# gpi-viper.net
KiCad netlist of a schematic drawn in EAGLE
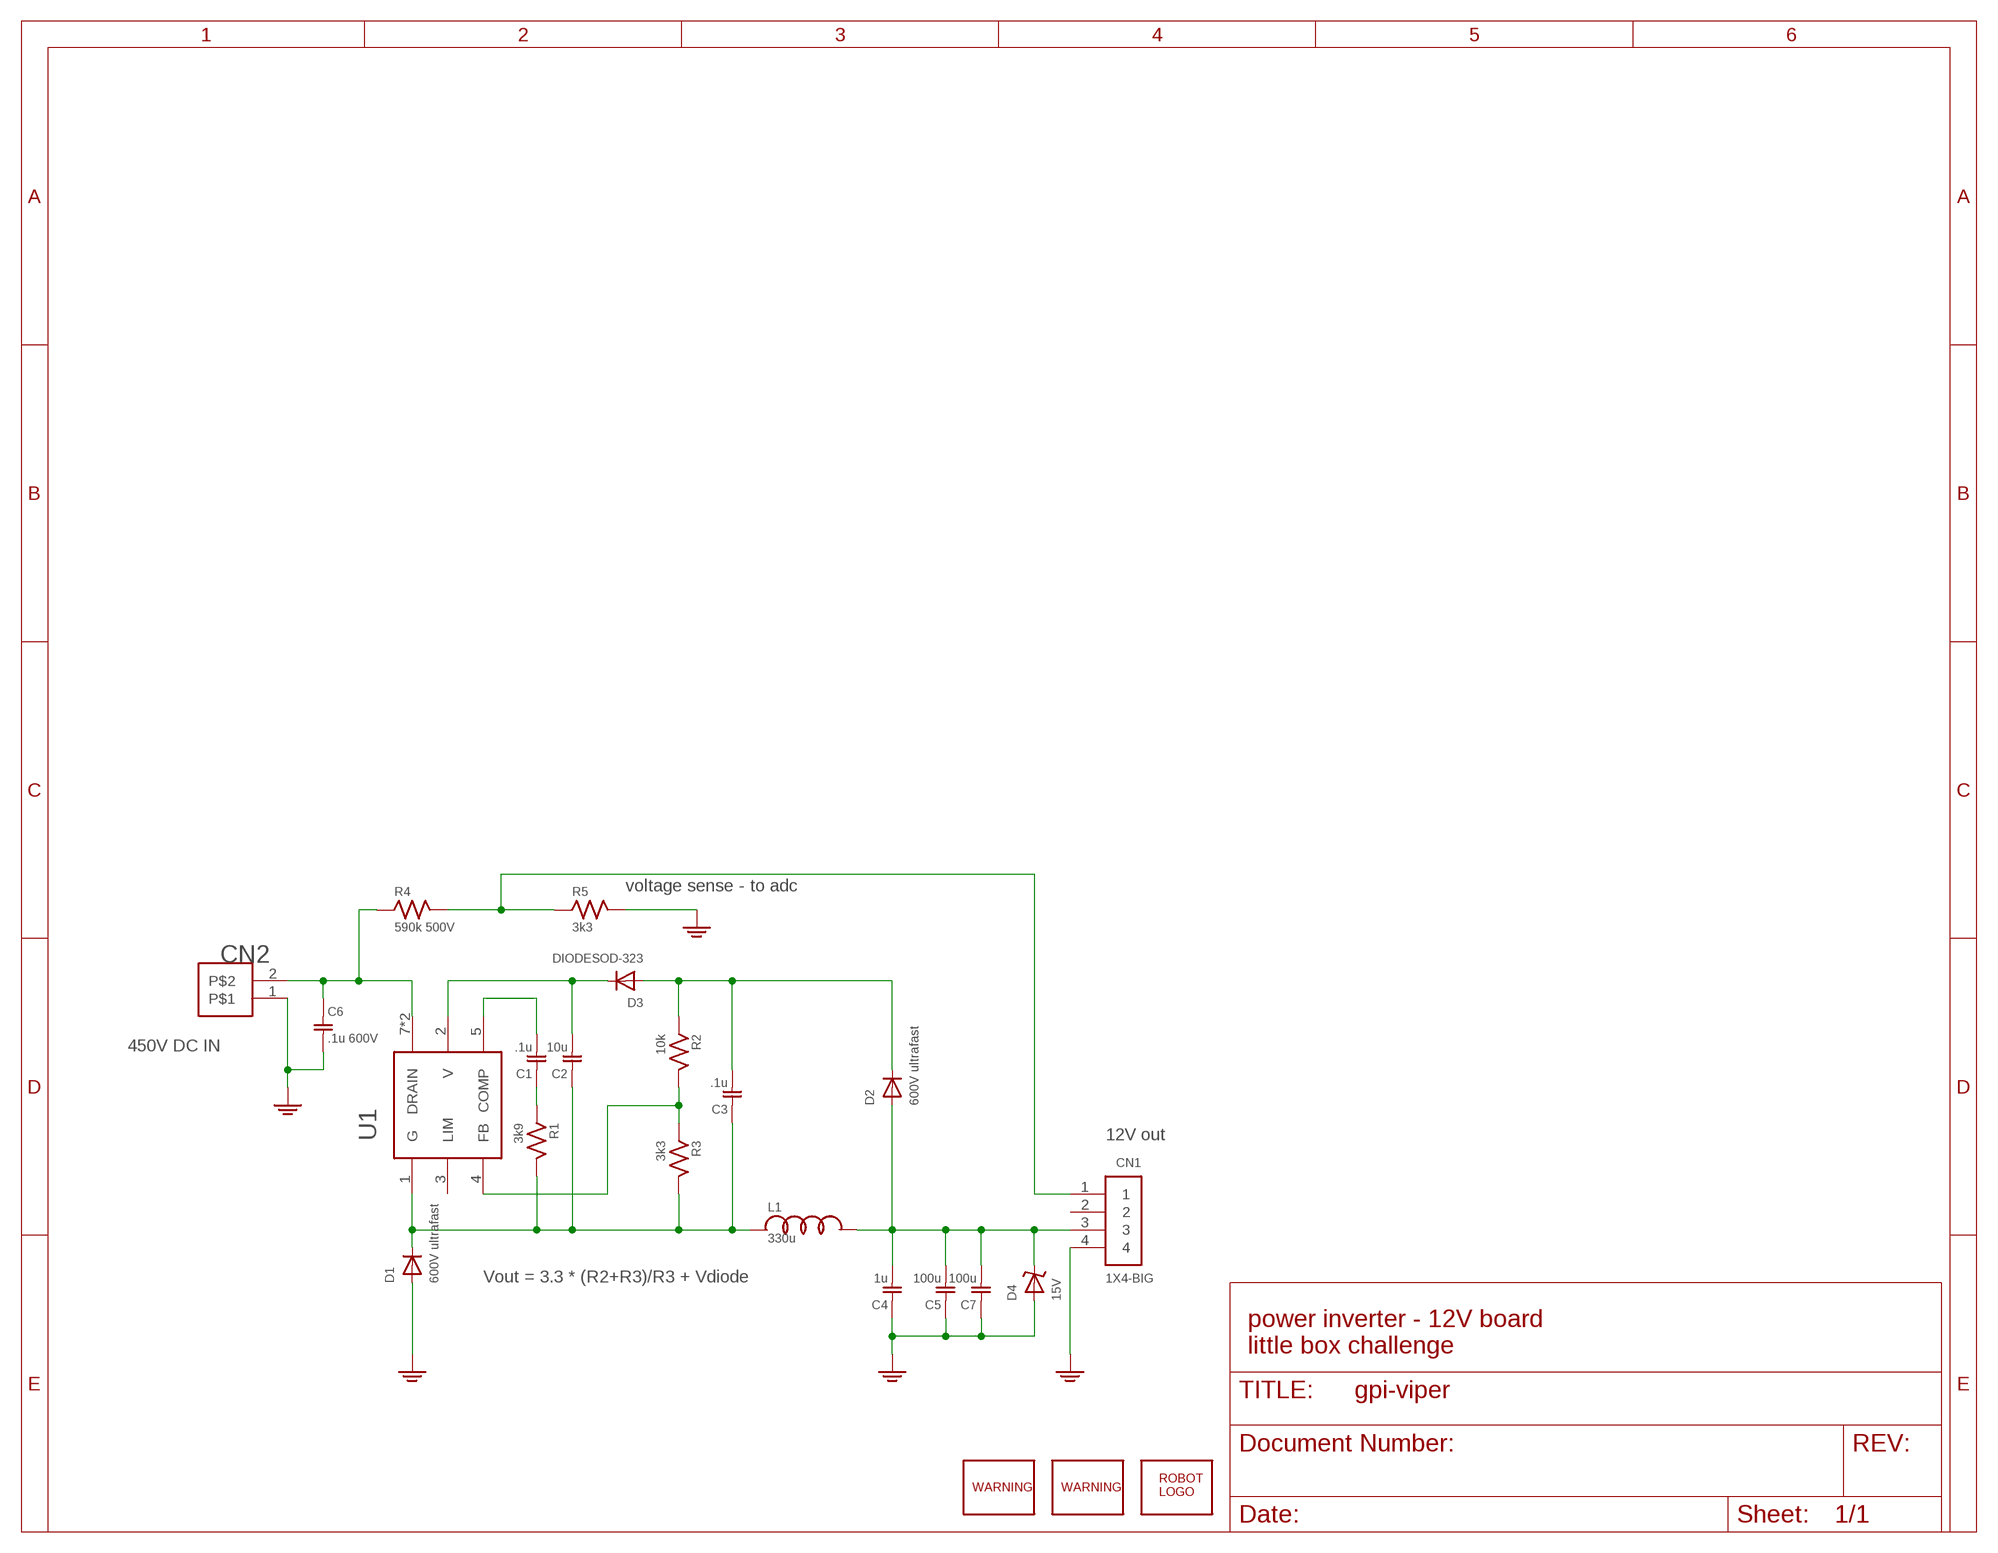
[diagram p0: schematic, sheet 1]

(export (version "E")
  (design (tool "Eeschema 10.0.6"))
  (components
    (comp (ref "C1")
      (value ".1u")
      (footprint "eagle-import:SMD0603")
      (libsource (lib "eagle-import") (part "C0603"))
    )
    (comp (ref "C2")
      (value "10u")
      (footprint "eagle-import:SMD0603")
      (libsource (lib "eagle-import") (part "C0603"))
    )
    (comp (ref "C3")
      (value ".1u")
      (footprint "eagle-import:SMD0603")
      (libsource (lib "eagle-import") (part "C0603"))
    )
    (comp (ref "C4")
      (value "1u")
      (footprint "eagle-import:SMD0603")
      (libsource (lib "eagle-import") (part "C0603"))
    )
    (comp (ref "C5")
      (value "100u")
      (footprint "eagle-import:SMD1210")
      (libsource (lib "eagle-import") (part "C1210"))
    )
    (comp (ref "C6")
      (value ".1u 600V")
      (footprint "eagle-import:SMD1210")
      (libsource (lib "eagle-import") (part "C1210"))
    )
    (comp (ref "C7")
      (value "100u")
      (footprint "eagle-import:SMD1210")
      (libsource (lib "eagle-import") (part "C1210"))
    )
    (comp (ref "CN1")
      (value "1X4-BIG")
      (footprint "eagle-import:1X04-BIG")
      (libsource (lib "eagle-import") (part "1X4-BIG"))
    )
    (comp (ref "CN2")
      (value "HEADER-1X2.4")
      (footprint "eagle-import:HEADER-1X2-THM-WIDE")
      (libsource (lib "eagle-import") (part "HEADER-1X2.4"))
    )
    (comp (ref "D1")
      (value "600V ultrafast")
      (footprint "eagle-import:DO-214AC")
      (libsource (lib "eagle-import") (part "DIODEDO-214AC"))
    )
    (comp (ref "D2")
      (value "600V ultrafast")
      (footprint "eagle-import:DO-214AC")
      (libsource (lib "eagle-import") (part "DIODEDO-214AC"))
    )
    (comp (ref "D3")
      (value "DIODESOD-323")
      (footprint "eagle-import:SOD-323")
      (libsource (lib "eagle-import") (part "DIODESOD-323"))
    )
    (comp (ref "D4")
      (value "15V")
      (footprint "eagle-import:SOD-323@1")
      (libsource (lib "eagle-import") (part "ZENER"))
    )
    (comp (ref "L1")
      (value "330u")
      (footprint "eagle-import:BOURNS2100")
      (libsource (lib "eagle-import") (part "L2100"))
    )
    (comp (ref "R1")
      (value "3k9")
      (footprint "eagle-import:SMD0603")
      (libsource (lib "eagle-import") (part "R0603"))
    )
    (comp (ref "R2")
      (value "10k")
      (footprint "eagle-import:SMD0603")
      (libsource (lib "eagle-import") (part "R0603"))
    )
    (comp (ref "R3")
      (value "3k3")
      (footprint "eagle-import:SMD0603")
      (libsource (lib "eagle-import") (part "R0603"))
    )
    (comp (ref "R4")
      (value "590k 500V")
      (footprint "eagle-import:SMD1206")
      (libsource (lib "eagle-import") (part "R1206"))
    )
    (comp (ref "R5")
      (value "3k3")
      (footprint "eagle-import:SMD0603")
      (libsource (lib "eagle-import") (part "R0603"))
    )
    (comp (ref "U$1")
      (value "ROBOTMAN-LOGO")
      (footprint "eagle-import:ROBOTMAN-LOGO")
      (libsource (lib "eagle-import") (part "ROBOTMAN-LOGO"))
    )
    (comp (ref "U$2")
      (value "SYMBOL-WARNING")
      (footprint "eagle-import:SYMBOL-WARNING")
      (libsource (lib "eagle-import") (part "SYMBOL-WARNING"))
    )
    (comp (ref "U$3")
      (value "SYMBOL-WARNING")
      (footprint "eagle-import:SYMBOL-WARNING")
      (libsource (lib "eagle-import") (part "SYMBOL-WARNING"))
    )
    (comp (ref "U1")
      (value "VIPER26DIP7")
      (footprint "eagle-import:VIPER26-P7")
      (libsource (lib "eagle-import") (part "VIPER26DIP7"))
    )
  )
  (nets
    (net (code "1") (name "Net-(C1-P$1)") (class "Default")
      (node (ref "C1") (pin "1") (pinfunction "P$1_1") (pintype "passive"))
      (node (ref "R1") (pin "1") (pinfunction "P$1_1") (pintype "passive"))
    )
    (net (code "2") (name "Net-(C1-P$2)") (class "Default")
      (node (ref "C1") (pin "2") (pinfunction "P$2_2") (pintype "passive"))
      (node (ref "U1") (pin "5") (pinfunction "COMP_5") (pintype "bidirectional"))
    )
    (net (code "3") (name "Net-(C2-P$1)") (class "Default")
      (node (ref "C2") (pin "1") (pinfunction "P$1_1") (pintype "passive"))
      (node (ref "C3") (pin "1") (pinfunction "P$1_1") (pintype "passive"))
      (node (ref "D1") (pin "C") (pinfunction "C_C") (pintype "passive"))
      (node (ref "L1") (pin "P$1") (pinfunction "P$1_P$1") (pintype "passive"))
      (node (ref "R1") (pin "2") (pinfunction "P$2_2") (pintype "passive"))
      (node (ref "R3") (pin "2") (pinfunction "P$2_2") (pintype "passive"))
      (node (ref "U1") (pin "1") (pinfunction "G_1") (pintype "bidirectional"))
    )
    (net (code "4") (name "Net-(C2-P$2)") (class "Default")
      (node (ref "C2") (pin "2") (pinfunction "P$2_2") (pintype "passive"))
      (node (ref "D3") (pin "C") (pinfunction "C_C") (pintype "passive"))
      (node (ref "U1") (pin "2") (pinfunction "V_2") (pintype "bidirectional"))
    )
    (net (code "5") (name "Net-(C3-P$2)") (class "Default")
      (node (ref "C3") (pin "2") (pinfunction "P$2_2") (pintype "passive"))
      (node (ref "D2") (pin "C") (pinfunction "C_C") (pintype "passive"))
      (node (ref "D3") (pin "A") (pinfunction "A_A") (pintype "passive"))
      (node (ref "R2") (pin "1") (pinfunction "P$1_1") (pintype "passive"))
    )
    (net (code "6") (name "Net-(C4-P$2)") (class "Default")
      (node (ref "C4") (pin "2") (pinfunction "P$2_2") (pintype "passive"))
      (node (ref "C5") (pin "2") (pinfunction "P$2_2") (pintype "passive"))
      (node (ref "C7") (pin "2") (pinfunction "P$2_2") (pintype "passive"))
      (node (ref "CN1") (pin "3") (pinfunction "3_3") (pintype "bidirectional"))
      (node (ref "D2") (pin "A") (pinfunction "A_A") (pintype "passive"))
      (node (ref "D4") (pin "C") (pinfunction "C_C") (pintype "passive"))
      (node (ref "L1") (pin "P$2") (pinfunction "P$2_P$2") (pintype "passive"))
    )
    (net (code "7") (name "Net-(C6-P$1)") (class "Default")
      (node (ref "C6") (pin "1") (pinfunction "P$1_1") (pintype "passive"))
      (node (ref "CN2") (pin "2") (pinfunction "P$2_2") (pintype "bidirectional"))
      (node (ref "R4") (pin "1") (pinfunction "P$1_1") (pintype "passive"))
      (node (ref "U1") (pin "7") (pinfunction "DRAIN_7") (pintype "bidirectional"))
      (node (ref "U1") (pin "8") (pinfunction "DRAIN_8") (pintype "bidirectional"))
    )
    (net (code "8") (name "Net-(R2-P$2)") (class "Default")
      (node (ref "R2") (pin "2") (pinfunction "P$2_2") (pintype "passive"))
      (node (ref "R3") (pin "1") (pinfunction "P$1_1") (pintype "passive"))
      (node (ref "U1") (pin "4") (pinfunction "FB_4") (pintype "bidirectional"))
    )
    (net (code "9") (name "Net-(R4-P$2)") (class "Default")
      (node (ref "CN1") (pin "1") (pinfunction "1_1") (pintype "bidirectional"))
      (node (ref "R4") (pin "2") (pinfunction "P$2_2") (pintype "passive"))
      (node (ref "R5") (pin "1") (pinfunction "P$1_1") (pintype "passive"))
    )
    (net (code "10") (name "PWR-GND") (class "Default")
      (node (ref "C4") (pin "1") (pinfunction "P$1_1") (pintype "passive"))
      (node (ref "C5") (pin "1") (pinfunction "P$1_1") (pintype "passive"))
      (node (ref "C6") (pin "2") (pinfunction "P$2_2") (pintype "passive"))
      (node (ref "C7") (pin "1") (pinfunction "P$1_1") (pintype "passive"))
      (node (ref "CN1") (pin "4") (pinfunction "4_4") (pintype "bidirectional"))
      (node (ref "CN2") (pin "1") (pinfunction "P$1_1") (pintype "bidirectional"))
      (node (ref "D1") (pin "A") (pinfunction "A_A") (pintype "passive"))
      (node (ref "D4") (pin "A") (pinfunction "A_A") (pintype "passive"))
      (node (ref "R5") (pin "2") (pinfunction "P$2_2") (pintype "passive"))
    )
    (net (code "11") (name "unconnected-(CN1-Pad2)") (class "Default")
      (node (ref "CN1") (pin "2") (pinfunction "2_2") (pintype "bidirectional"))
    )
    (net (code "12") (name "unconnected-(U1-LIM-Pad3)") (class "Default")
      (node (ref "U1") (pin "3") (pinfunction "LIM_3") (pintype "bidirectional"))
    )
  )
)
